# sch.net
KiCad netlist of a schematic drawn in EAGLE
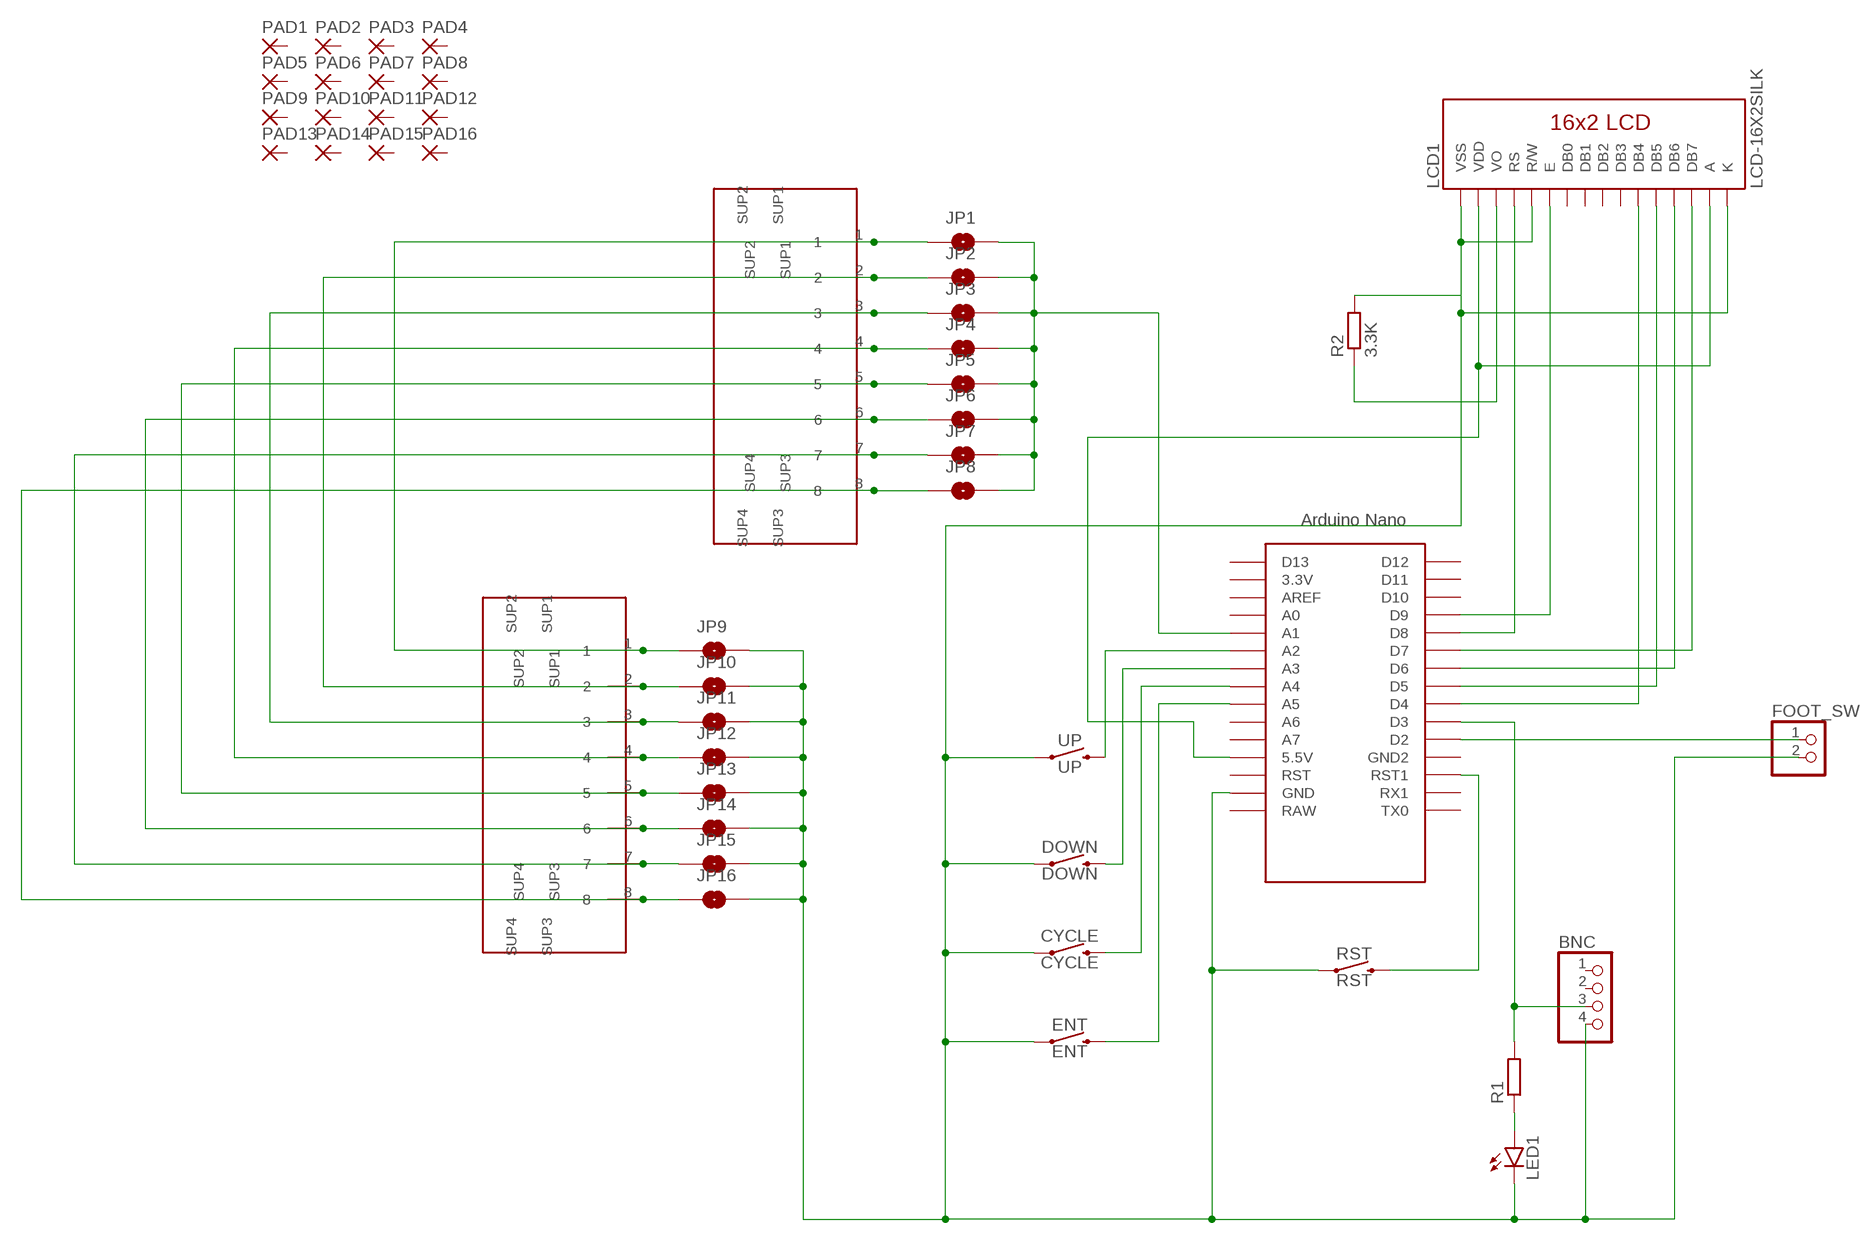
[diagram p0: schematic, sheet 1]

(export (version "E")
  (design (tool "Eeschema 10.0.6"))
  (components
    (comp (ref "BNC")
      (value "PINHD-1X4")
      (footprint "eagle-import:1X04")
      (libsource (lib "eagle-import") (part "PINHD-1X4"))
    )
    (comp (ref "CYCLE")
      (value "CYCLE")
      (footprint "eagle-import:TACTILE_SWITCH_PTH_6.0MM")
      (libsource (lib "eagle-import") (part "MOMENTARY-SWITCH-SPST-PTH-6.0MM"))
    )
    (comp (ref "DOWN")
      (value "DOWN")
      (footprint "eagle-import:TACTILE_SWITCH_PTH_6.0MM")
      (libsource (lib "eagle-import") (part "MOMENTARY-SWITCH-SPST-PTH-6.0MM"))
    )
    (comp (ref "ENT")
      (value "ENT")
      (footprint "eagle-import:TACTILE_SWITCH_PTH_6.0MM")
      (libsource (lib "eagle-import") (part "MOMENTARY-SWITCH-SPST-PTH-6.0MM"))
    )
    (comp (ref "FOOT_SW")
      (value "PINHD-1X2")
      (footprint "eagle-import:1X02")
      (libsource (lib "eagle-import") (part "PINHD-1X2"))
    )
    (comp (ref "JP1")
      (value "JUMPER-SMT_2_NO_SILK")
      (footprint "eagle-import:SMT-JUMPER_2_NO_SILK")
      (libsource (lib "eagle-import") (part "JUMPER-SMT_2_NO_SILK"))
    )
    (comp (ref "JP2")
      (value "JUMPER-SMT_2_NO_SILK")
      (footprint "eagle-import:SMT-JUMPER_2_NO_SILK")
      (libsource (lib "eagle-import") (part "JUMPER-SMT_2_NO_SILK"))
    )
    (comp (ref "JP3")
      (value "JUMPER-SMT_2_NO_SILK")
      (footprint "eagle-import:SMT-JUMPER_2_NO_SILK")
      (libsource (lib "eagle-import") (part "JUMPER-SMT_2_NO_SILK"))
    )
    (comp (ref "JP4")
      (value "JUMPER-SMT_2_NO_SILK")
      (footprint "eagle-import:SMT-JUMPER_2_NO_SILK")
      (libsource (lib "eagle-import") (part "JUMPER-SMT_2_NO_SILK"))
    )
    (comp (ref "JP5")
      (value "JUMPER-SMT_2_NO_SILK")
      (footprint "eagle-import:SMT-JUMPER_2_NO_SILK")
      (libsource (lib "eagle-import") (part "JUMPER-SMT_2_NO_SILK"))
    )
    (comp (ref "JP6")
      (value "JUMPER-SMT_2_NO_SILK")
      (footprint "eagle-import:SMT-JUMPER_2_NO_SILK")
      (libsource (lib "eagle-import") (part "JUMPER-SMT_2_NO_SILK"))
    )
    (comp (ref "JP7")
      (value "JUMPER-SMT_2_NO_SILK")
      (footprint "eagle-import:SMT-JUMPER_2_NO_SILK")
      (libsource (lib "eagle-import") (part "JUMPER-SMT_2_NO_SILK"))
    )
    (comp (ref "JP8")
      (value "JUMPER-SMT_2_NO_SILK")
      (footprint "eagle-import:SMT-JUMPER_2_NO_SILK")
      (libsource (lib "eagle-import") (part "JUMPER-SMT_2_NO_SILK"))
    )
    (comp (ref "JP9")
      (value "JUMPER-SMT_2_NO_SILK")
      (footprint "eagle-import:SMT-JUMPER_2_NO_SILK")
      (libsource (lib "eagle-import") (part "JUMPER-SMT_2_NO_SILK"))
    )
    (comp (ref "JP10")
      (value "JUMPER-SMT_2_NO_SILK")
      (footprint "eagle-import:SMT-JUMPER_2_NO_SILK")
      (libsource (lib "eagle-import") (part "JUMPER-SMT_2_NO_SILK"))
    )
    (comp (ref "JP11")
      (value "JUMPER-SMT_2_NO_SILK")
      (footprint "eagle-import:SMT-JUMPER_2_NO_SILK")
      (libsource (lib "eagle-import") (part "JUMPER-SMT_2_NO_SILK"))
    )
    (comp (ref "JP12")
      (value "JUMPER-SMT_2_NO_SILK")
      (footprint "eagle-import:SMT-JUMPER_2_NO_SILK")
      (libsource (lib "eagle-import") (part "JUMPER-SMT_2_NO_SILK"))
    )
    (comp (ref "JP13")
      (value "JUMPER-SMT_2_NO_SILK")
      (footprint "eagle-import:SMT-JUMPER_2_NO_SILK")
      (libsource (lib "eagle-import") (part "JUMPER-SMT_2_NO_SILK"))
    )
    (comp (ref "JP14")
      (value "JUMPER-SMT_2_NO_SILK")
      (footprint "eagle-import:SMT-JUMPER_2_NO_SILK")
      (libsource (lib "eagle-import") (part "JUMPER-SMT_2_NO_SILK"))
    )
    (comp (ref "JP15")
      (value "JUMPER-SMT_2_NO_SILK")
      (footprint "eagle-import:SMT-JUMPER_2_NO_SILK")
      (libsource (lib "eagle-import") (part "JUMPER-SMT_2_NO_SILK"))
    )
    (comp (ref "JP16")
      (value "JUMPER-SMT_2_NO_SILK")
      (footprint "eagle-import:SMT-JUMPER_2_NO_SILK")
      (libsource (lib "eagle-import") (part "JUMPER-SMT_2_NO_SILK"))
    )
    (comp (ref "LAN1")
      (value "RJ45")
      (footprint "eagle-import:RJ45")
      (libsource (lib "eagle-import") (part "RJ45"))
    )
    (comp (ref "LAN2")
      (value "RJ45")
      (footprint "eagle-import:RJ45")
      (libsource (lib "eagle-import") (part "RJ45"))
    )
    (comp (ref "LCD1")
      (value "LCD-16X2SILK")
      (footprint "eagle-import:LCD-16X2")
      (libsource (lib "eagle-import") (part "LCD-16X2SILK"))
    )
    (comp (ref "LED1")
      (value "LED5MM")
      (footprint "eagle-import:LED5MM")
      (libsource (lib "eagle-import") (part "LED5MM"))
    )
    (comp (ref "PAD1")
      (value "1,6/0,8")
      (footprint "eagle-import:1,6_0,8")
      (libsource (lib "eagle-import") (part "1,6/0,8"))
    )
    (comp (ref "PAD2")
      (value "1,6/0,8")
      (footprint "eagle-import:1,6_0,8")
      (libsource (lib "eagle-import") (part "1,6/0,8"))
    )
    (comp (ref "PAD3")
      (value "1,6/0,8")
      (footprint "eagle-import:1,6_0,8")
      (libsource (lib "eagle-import") (part "1,6/0,8"))
    )
    (comp (ref "PAD4")
      (value "1,6/0,8")
      (footprint "eagle-import:1,6_0,8")
      (libsource (lib "eagle-import") (part "1,6/0,8"))
    )
    (comp (ref "PAD5")
      (value "1,6/0,8")
      (footprint "eagle-import:1,6_0,8")
      (libsource (lib "eagle-import") (part "1,6/0,8"))
    )
    (comp (ref "PAD6")
      (value "1,6/0,8")
      (footprint "eagle-import:1,6_0,8")
      (libsource (lib "eagle-import") (part "1,6/0,8"))
    )
    (comp (ref "PAD7")
      (value "1,6/0,8")
      (footprint "eagle-import:1,6_0,8")
      (libsource (lib "eagle-import") (part "1,6/0,8"))
    )
    (comp (ref "PAD8")
      (value "1,6/0,8")
      (footprint "eagle-import:1,6_0,8")
      (libsource (lib "eagle-import") (part "1,6/0,8"))
    )
    (comp (ref "PAD9")
      (value "1,6/0,8")
      (footprint "eagle-import:1,6_0,8")
      (libsource (lib "eagle-import") (part "1,6/0,8"))
    )
    (comp (ref "PAD10")
      (value "1,6/0,8")
      (footprint "eagle-import:1,6_0,8")
      (libsource (lib "eagle-import") (part "1,6/0,8"))
    )
    (comp (ref "PAD11")
      (value "1,6/0,8")
      (footprint "eagle-import:1,6_0,8")
      (libsource (lib "eagle-import") (part "1,6/0,8"))
    )
    (comp (ref "PAD12")
      (value "1,6/0,8")
      (footprint "eagle-import:1,6_0,8")
      (libsource (lib "eagle-import") (part "1,6/0,8"))
    )
    (comp (ref "PAD13")
      (value "1,6/0,8")
      (footprint "eagle-import:1,6_0,8")
      (libsource (lib "eagle-import") (part "1,6/0,8"))
    )
    (comp (ref "PAD14")
      (value "1,6/0,8")
      (footprint "eagle-import:1,6_0,8")
      (libsource (lib "eagle-import") (part "1,6/0,8"))
    )
    (comp (ref "PAD15")
      (value "1,6/0,8")
      (footprint "eagle-import:1,6_0,8")
      (libsource (lib "eagle-import") (part "1,6/0,8"))
    )
    (comp (ref "PAD16")
      (value "1,6/0,8")
      (footprint "eagle-import:1,6_0,8")
      (libsource (lib "eagle-import") (part "1,6/0,8"))
    )
    (comp (ref "R1")
      (value "R-EU_0207/7")
      (footprint "eagle-import:0207_7")
      (libsource (lib "eagle-import") (part "R-EU_0207/7"))
    )
    (comp (ref "R2")
      (value "3.3K")
      (footprint "eagle-import:0207_7")
      (libsource (lib "eagle-import") (part "R-EU_0207/7"))
    )
    (comp (ref "RST")
      (value "RST")
      (footprint "eagle-import:TACTILE_SWITCH_PTH_6.0MM")
      (libsource (lib "eagle-import") (part "MOMENTARY-SWITCH-SPST-PTH-6.0MM"))
    )
    (comp (ref "U$1")
      (value "NANO")
      (footprint "eagle-import:NANO")
      (libsource (lib "eagle-import") (part "NANO"))
    )
    (comp (ref "UP")
      (value "UP")
      (footprint "eagle-import:TACTILE_SWITCH_PTH_6.0MM")
      (libsource (lib "eagle-import") (part "MOMENTARY-SWITCH-SPST-PTH-6.0MM"))
    )
  )
  (nets
    (net (code "1") (name "Net-(BNC-Pad3)") (class "Default")
      (node (ref "BNC") (pin "3") (pinfunction "3_3") (pintype "passive"))
      (node (ref "R1") (pin "2") (pinfunction "2_2") (pintype "passive"))
      (node (ref "U$1") (pin "D3") (pinfunction "D3_D3") (pintype "bidirectional"))
    )
    (net (code "2") (name "Net-(CYCLE-2)") (class "Default")
      (node (ref "CYCLE") (pin "3") (pinfunction "2_3") (pintype "passive"))
      (node (ref "U$1") (pin "A4") (pinfunction "A4_A4") (pintype "bidirectional"))
    )
    (net (code "3") (name "Net-(DOWN-2)") (class "Default")
      (node (ref "DOWN") (pin "3") (pinfunction "2_3") (pintype "passive"))
      (node (ref "U$1") (pin "A3") (pinfunction "A3_A3") (pintype "bidirectional"))
    )
    (net (code "4") (name "Net-(ENT-2)") (class "Default")
      (node (ref "ENT") (pin "3") (pinfunction "2_3") (pintype "passive"))
      (node (ref "U$1") (pin "A5") (pinfunction "A5_A5") (pintype "bidirectional"))
    )
    (net (code "5") (name "Net-(FOOT_SW-Pad1)") (class "Default")
      (node (ref "FOOT_SW") (pin "1") (pinfunction "1_1") (pintype "passive"))
      (node (ref "U$1") (pin "D2") (pinfunction "D2_D2") (pintype "bidirectional"))
    )
    (net (code "6") (name "Net-(JP1-Pad1)") (class "Default")
      (node (ref "JP1") (pin "1") (pinfunction "1_1") (pintype "passive"))
      (node (ref "JP9") (pin "1") (pinfunction "1_1") (pintype "passive"))
      (node (ref "LAN1") (pin "1") (pinfunction "1_1") (pintype "bidirectional"))
      (node (ref "LAN2") (pin "1") (pinfunction "1_1") (pintype "bidirectional"))
    )
    (net (code "7") (name "Net-(JP1-Pad2)") (class "Default")
      (node (ref "JP1") (pin "2") (pinfunction "2_2") (pintype "passive"))
      (node (ref "JP2") (pin "2") (pinfunction "2_2") (pintype "passive"))
      (node (ref "JP3") (pin "2") (pinfunction "2_2") (pintype "passive"))
      (node (ref "JP4") (pin "2") (pinfunction "2_2") (pintype "passive"))
      (node (ref "JP5") (pin "2") (pinfunction "2_2") (pintype "passive"))
      (node (ref "JP6") (pin "2") (pinfunction "2_2") (pintype "passive"))
      (node (ref "JP7") (pin "2") (pinfunction "2_2") (pintype "passive"))
      (node (ref "JP8") (pin "2") (pinfunction "2_2") (pintype "passive"))
      (node (ref "U$1") (pin "A1") (pinfunction "A1_A1") (pintype "bidirectional"))
    )
    (net (code "8") (name "Net-(JP10-Pad1)") (class "Default")
      (node (ref "JP10") (pin "1") (pinfunction "1_1") (pintype "passive"))
      (node (ref "JP2") (pin "1") (pinfunction "1_1") (pintype "passive"))
      (node (ref "LAN1") (pin "2") (pinfunction "2_2") (pintype "bidirectional"))
      (node (ref "LAN2") (pin "2") (pinfunction "2_2") (pintype "bidirectional"))
    )
    (net (code "9") (name "Net-(JP11-Pad1)") (class "Default")
      (node (ref "JP11") (pin "1") (pinfunction "1_1") (pintype "passive"))
      (node (ref "JP3") (pin "1") (pinfunction "1_1") (pintype "passive"))
      (node (ref "LAN1") (pin "3") (pinfunction "3_3") (pintype "bidirectional"))
      (node (ref "LAN2") (pin "3") (pinfunction "3_3") (pintype "bidirectional"))
    )
    (net (code "10") (name "Net-(JP12-Pad1)") (class "Default")
      (node (ref "JP12") (pin "1") (pinfunction "1_1") (pintype "passive"))
      (node (ref "JP4") (pin "1") (pinfunction "1_1") (pintype "passive"))
      (node (ref "LAN1") (pin "4") (pinfunction "4_4") (pintype "bidirectional"))
      (node (ref "LAN2") (pin "4") (pinfunction "4_4") (pintype "bidirectional"))
    )
    (net (code "11") (name "Net-(JP13-Pad1)") (class "Default")
      (node (ref "JP13") (pin "1") (pinfunction "1_1") (pintype "passive"))
      (node (ref "JP5") (pin "1") (pinfunction "1_1") (pintype "passive"))
      (node (ref "LAN1") (pin "5") (pinfunction "5_5") (pintype "bidirectional"))
      (node (ref "LAN2") (pin "5") (pinfunction "5_5") (pintype "bidirectional"))
    )
    (net (code "12") (name "Net-(JP14-Pad1)") (class "Default")
      (node (ref "JP14") (pin "1") (pinfunction "1_1") (pintype "passive"))
      (node (ref "JP6") (pin "1") (pinfunction "1_1") (pintype "passive"))
      (node (ref "LAN1") (pin "6") (pinfunction "6_6") (pintype "bidirectional"))
      (node (ref "LAN2") (pin "6") (pinfunction "6_6") (pintype "bidirectional"))
    )
    (net (code "13") (name "Net-(JP15-Pad1)") (class "Default")
      (node (ref "JP15") (pin "1") (pinfunction "1_1") (pintype "passive"))
      (node (ref "JP7") (pin "1") (pinfunction "1_1") (pintype "passive"))
      (node (ref "LAN1") (pin "7") (pinfunction "7_7") (pintype "bidirectional"))
      (node (ref "LAN2") (pin "7") (pinfunction "7_7") (pintype "bidirectional"))
    )
    (net (code "14") (name "Net-(JP16-Pad1)") (class "Default")
      (node (ref "JP16") (pin "1") (pinfunction "1_1") (pintype "passive"))
      (node (ref "JP8") (pin "1") (pinfunction "1_1") (pintype "passive"))
      (node (ref "LAN1") (pin "8") (pinfunction "8_8") (pintype "bidirectional"))
      (node (ref "LAN2") (pin "8") (pinfunction "8_8") (pintype "bidirectional"))
    )
    (net (code "15") (name "Net-(LCD1-A)") (class "Default")
      (node (ref "LCD1") (pin "15") (pinfunction "A_15") (pintype "power_in"))
      (node (ref "LCD1") (pin "2") (pinfunction "VDD_2") (pintype "power_in"))
      (node (ref "U$1") (pin "5V") (pinfunction "5.5V_5V") (pintype "bidirectional"))
    )
    (net (code "16") (name "Net-(LCD1-DB4)") (class "Default")
      (node (ref "LCD1") (pin "11") (pinfunction "DB4_11") (pintype "bidirectional"))
      (node (ref "U$1") (pin "D4") (pinfunction "D4_D4") (pintype "bidirectional"))
    )
    (net (code "17") (name "Net-(LCD1-DB5)") (class "Default")
      (node (ref "LCD1") (pin "12") (pinfunction "DB5_12") (pintype "bidirectional"))
      (node (ref "U$1") (pin "D5") (pinfunction "D5_D5") (pintype "bidirectional"))
    )
    (net (code "18") (name "Net-(LCD1-DB6)") (class "Default")
      (node (ref "LCD1") (pin "13") (pinfunction "DB6_13") (pintype "bidirectional"))
      (node (ref "U$1") (pin "D6") (pinfunction "D6_D6") (pintype "bidirectional"))
    )
    (net (code "19") (name "Net-(LCD1-DB7)") (class "Default")
      (node (ref "LCD1") (pin "14") (pinfunction "DB7_14") (pintype "bidirectional"))
      (node (ref "U$1") (pin "D7") (pinfunction "D7_D7") (pintype "bidirectional"))
    )
    (net (code "20") (name "Net-(LCD1-E)") (class "Default")
      (node (ref "LCD1") (pin "6") (pinfunction "E_6") (pintype "input"))
      (node (ref "U$1") (pin "D9") (pinfunction "D9_D9") (pintype "bidirectional"))
    )
    (net (code "21") (name "Net-(LCD1-K)") (class "Default")
      (node (ref "BNC") (pin "4") (pinfunction "4_4") (pintype "passive"))
      (node (ref "CYCLE") (pin "1") (pinfunction "1_1") (pintype "passive"))
      (node (ref "DOWN") (pin "1") (pinfunction "1_1") (pintype "passive"))
      (node (ref "ENT") (pin "1") (pinfunction "1_1") (pintype "passive"))
      (node (ref "FOOT_SW") (pin "2") (pinfunction "2_2") (pintype "passive"))
      (node (ref "JP10") (pin "2") (pinfunction "2_2") (pintype "passive"))
      (node (ref "JP11") (pin "2") (pinfunction "2_2") (pintype "passive"))
      (node (ref "JP12") (pin "2") (pinfunction "2_2") (pintype "passive"))
      (node (ref "JP13") (pin "2") (pinfunction "2_2") (pintype "passive"))
      (node (ref "JP14") (pin "2") (pinfunction "2_2") (pintype "passive"))
      (node (ref "JP15") (pin "2") (pinfunction "2_2") (pintype "passive"))
      (node (ref "JP16") (pin "2") (pinfunction "2_2") (pintype "passive"))
      (node (ref "JP9") (pin "2") (pinfunction "2_2") (pintype "passive"))
      (node (ref "LCD1") (pin "1") (pinfunction "VSS_1") (pintype "power_in"))
      (node (ref "LCD1") (pin "16") (pinfunction "K_16") (pintype "power_in"))
      (node (ref "LCD1") (pin "5") (pinfunction "R/W_5") (pintype "input"))
      (node (ref "LED1") (pin "K") (pinfunction "C_K") (pintype "passive"))
      (node (ref "R2") (pin "2") (pinfunction "2_2") (pintype "passive"))
      (node (ref "RST") (pin "1") (pinfunction "1_1") (pintype "passive"))
      (node (ref "U$1") (pin "GND") (pinfunction "GND_GND") (pintype "bidirectional"))
      (node (ref "UP") (pin "1") (pinfunction "1_1") (pintype "passive"))
    )
    (net (code "22") (name "Net-(LCD1-RS)") (class "Default")
      (node (ref "LCD1") (pin "4") (pinfunction "RS_4") (pintype "input"))
      (node (ref "U$1") (pin "D8") (pinfunction "D8_D8") (pintype "bidirectional"))
    )
    (net (code "23") (name "Net-(LCD1-VO)") (class "Default")
      (node (ref "LCD1") (pin "3") (pinfunction "VO_3") (pintype "bidirectional"))
      (node (ref "R2") (pin "1") (pinfunction "1_1") (pintype "passive"))
    )
    (net (code "24") (name "Net-(LED1-PadA)") (class "Default")
      (node (ref "LED1") (pin "A") (pinfunction "A_A") (pintype "passive"))
      (node (ref "R1") (pin "1") (pinfunction "1_1") (pintype "passive"))
    )
    (net (code "25") (name "Net-(RST-2)") (class "Default")
      (node (ref "RST") (pin "3") (pinfunction "2_3") (pintype "passive"))
      (node (ref "U$1") (pin "RST1") (pinfunction "RST1_RST1") (pintype "bidirectional"))
    )
    (net (code "26") (name "Net-(UP-2)") (class "Default")
      (node (ref "U$1") (pin "A2") (pinfunction "A2_A2") (pintype "bidirectional"))
      (node (ref "UP") (pin "3") (pinfunction "2_3") (pintype "passive"))
    )
    (net (code "27") (name "unconnected-(BNC-Pad1)") (class "Default")
      (node (ref "BNC") (pin "1") (pinfunction "1_1") (pintype "passive"))
    )
    (net (code "28") (name "unconnected-(BNC-Pad2)") (class "Default")
      (node (ref "BNC") (pin "2") (pinfunction "2_2") (pintype "passive"))
    )
    (net (code "29") (name "unconnected-(LAN1-PadSUP1)") (class "Default")
      (node (ref "LAN1") (pin "SUP1") (pinfunction "SUP1_SUP1") (pintype "bidirectional"))
    )
    (net (code "30") (name "unconnected-(LAN1-PadSUP2)") (class "Default")
      (node (ref "LAN1") (pin "SUP2") (pinfunction "SUP2_SUP2") (pintype "bidirectional"))
    )
    (net (code "31") (name "unconnected-(LAN1-PadSUP3)") (class "Default")
      (node (ref "LAN1") (pin "SUP3") (pinfunction "SUP3_SUP3") (pintype "bidirectional"))
    )
    (net (code "32") (name "unconnected-(LAN1-PadSUP4)") (class "Default")
      (node (ref "LAN1") (pin "SUP4") (pinfunction "SUP4_SUP4") (pintype "bidirectional"))
    )
    (net (code "33") (name "unconnected-(LAN2-PadSUP1)") (class "Default")
      (node (ref "LAN2") (pin "SUP1") (pinfunction "SUP1_SUP1") (pintype "bidirectional"))
    )
    (net (code "34") (name "unconnected-(LAN2-PadSUP2)") (class "Default")
      (node (ref "LAN2") (pin "SUP2") (pinfunction "SUP2_SUP2") (pintype "bidirectional"))
    )
    (net (code "35") (name "unconnected-(LAN2-PadSUP3)") (class "Default")
      (node (ref "LAN2") (pin "SUP3") (pinfunction "SUP3_SUP3") (pintype "bidirectional"))
    )
    (net (code "36") (name "unconnected-(LAN2-PadSUP4)") (class "Default")
      (node (ref "LAN2") (pin "SUP4") (pinfunction "SUP4_SUP4") (pintype "bidirectional"))
    )
    (net (code "37") (name "unconnected-(LCD1-DB0-Pad7)") (class "Default")
      (node (ref "LCD1") (pin "7") (pinfunction "DB0_7") (pintype "bidirectional"))
    )
    (net (code "38") (name "unconnected-(LCD1-DB1-Pad8)") (class "Default")
      (node (ref "LCD1") (pin "8") (pinfunction "DB1_8") (pintype "bidirectional"))
    )
    (net (code "39") (name "unconnected-(LCD1-DB2-Pad9)") (class "Default")
      (node (ref "LCD1") (pin "9") (pinfunction "DB2_9") (pintype "bidirectional"))
    )
    (net (code "40") (name "unconnected-(LCD1-DB3-Pad10)") (class "Default")
      (node (ref "LCD1") (pin "10") (pinfunction "DB3_10") (pintype "bidirectional"))
    )
    (net (code "41") (name "unconnected-(PAD1-P-Pad1)") (class "Default")
      (node (ref "PAD1") (pin "1") (pinfunction "P_1") (pintype "passive"))
    )
    (net (code "42") (name "unconnected-(PAD2-P-Pad1)") (class "Default")
      (node (ref "PAD2") (pin "1") (pinfunction "P_1") (pintype "passive"))
    )
    (net (code "43") (name "unconnected-(PAD3-P-Pad1)") (class "Default")
      (node (ref "PAD3") (pin "1") (pinfunction "P_1") (pintype "passive"))
    )
    (net (code "44") (name "unconnected-(PAD4-P-Pad1)") (class "Default")
      (node (ref "PAD4") (pin "1") (pinfunction "P_1") (pintype "passive"))
    )
    (net (code "45") (name "unconnected-(PAD5-P-Pad1)") (class "Default")
      (node (ref "PAD5") (pin "1") (pinfunction "P_1") (pintype "passive"))
    )
    (net (code "46") (name "unconnected-(PAD6-P-Pad1)") (class "Default")
      (node (ref "PAD6") (pin "1") (pinfunction "P_1") (pintype "passive"))
    )
    (net (code "47") (name "unconnected-(PAD7-P-Pad1)") (class "Default")
      (node (ref "PAD7") (pin "1") (pinfunction "P_1") (pintype "passive"))
    )
    (net (code "48") (name "unconnected-(PAD8-P-Pad1)") (class "Default")
      (node (ref "PAD8") (pin "1") (pinfunction "P_1") (pintype "passive"))
    )
    (net (code "49") (name "unconnected-(PAD9-P-Pad1)") (class "Default")
      (node (ref "PAD9") (pin "1") (pinfunction "P_1") (pintype "passive"))
    )
    (net (code "50") (name "unconnected-(PAD10-P-Pad1)") (class "Default")
      (node (ref "PAD10") (pin "1") (pinfunction "P_1") (pintype "passive"))
    )
    (net (code "51") (name "unconnected-(PAD11-P-Pad1)") (class "Default")
      (node (ref "PAD11") (pin "1") (pinfunction "P_1") (pintype "passive"))
    )
    (net (code "52") (name "unconnected-(PAD12-P-Pad1)") (class "Default")
      (node (ref "PAD12") (pin "1") (pinfunction "P_1") (pintype "passive"))
    )
    (net (code "53") (name "unconnected-(PAD13-P-Pad1)") (class "Default")
      (node (ref "PAD13") (pin "1") (pinfunction "P_1") (pintype "passive"))
    )
    (net (code "54") (name "unconnected-(PAD14-P-Pad1)") (class "Default")
      (node (ref "PAD14") (pin "1") (pinfunction "P_1") (pintype "passive"))
    )
    (net (code "55") (name "unconnected-(PAD15-P-Pad1)") (class "Default")
      (node (ref "PAD15") (pin "1") (pinfunction "P_1") (pintype "passive"))
    )
    (net (code "56") (name "unconnected-(PAD16-P-Pad1)") (class "Default")
      (node (ref "PAD16") (pin "1") (pinfunction "P_1") (pintype "passive"))
    )
    (net (code "57") (name "unconnected-(U$1-GND2-PadGND1)") (class "Default")
      (node (ref "U$1") (pin "GND1") (pinfunction "GND2_GND1") (pintype "bidirectional"))
    )
    (net (code "58") (name "unconnected-(U$1-Pad3.3V)") (class "Default")
      (node (ref "U$1") (pin "3.3V") (pinfunction "3.3V_3.3V") (pintype "bidirectional"))
    )
    (net (code "59") (name "unconnected-(U$1-PadA0)") (class "Default")
      (node (ref "U$1") (pin "A0") (pinfunction "A0_A0") (pintype "bidirectional"))
    )
    (net (code "60") (name "unconnected-(U$1-PadA6)") (class "Default")
      (node (ref "U$1") (pin "A6") (pinfunction "A6_A6") (pintype "bidirectional"))
    )
    (net (code "61") (name "unconnected-(U$1-PadA7)") (class "Default")
      (node (ref "U$1") (pin "A7") (pinfunction "A7_A7") (pintype "bidirectional"))
    )
    (net (code "62") (name "unconnected-(U$1-PadAREF)") (class "Default")
      (node (ref "U$1") (pin "AREF") (pinfunction "AREF_AREF") (pintype "bidirectional"))
    )
    (net (code "63") (name "unconnected-(U$1-PadD10)") (class "Default")
      (node (ref "U$1") (pin "D10") (pinfunction "D10_D10") (pintype "bidirectional"))
    )
    (net (code "64") (name "unconnected-(U$1-PadD11)") (class "Default")
      (node (ref "U$1") (pin "D11") (pinfunction "D11_D11") (pintype "bidirectional"))
    )
    (net (code "65") (name "unconnected-(U$1-PadD12)") (class "Default")
      (node (ref "U$1") (pin "D12") (pinfunction "D12_D12") (pintype "bidirectional"))
    )
    (net (code "66") (name "unconnected-(U$1-PadD13)") (class "Default")
      (node (ref "U$1") (pin "D13") (pinfunction "D13_D13") (pintype "bidirectional"))
    )
    (net (code "67") (name "unconnected-(U$1-PadICSP1)") (class "Default")
      (node (ref "U$1") (pin "ICSP1") (pinfunction "ICSP1_ICSP1") (pintype "bidirectional"))
    )
    (net (code "68") (name "unconnected-(U$1-PadICSP2)") (class "Default")
      (node (ref "U$1") (pin "ICSP2") (pinfunction "ICSP2_ICSP2") (pintype "bidirectional"))
    )
    (net (code "69") (name "unconnected-(U$1-PadICSP3)") (class "Default")
      (node (ref "U$1") (pin "ICSP3") (pinfunction "ICSP3_ICSP3") (pintype "bidirectional"))
    )
    (net (code "70") (name "unconnected-(U$1-PadICSP4)") (class "Default")
      (node (ref "U$1") (pin "ICSP4") (pinfunction "ICSP4_ICSP4") (pintype "bidirectional"))
    )
    (net (code "71") (name "unconnected-(U$1-PadICSP5)") (class "Default")
      (node (ref "U$1") (pin "ICSP5") (pinfunction "ICSP5_ICSP5") (pintype "bidirectional"))
    )
    (net (code "72") (name "unconnected-(U$1-PadICSP6)") (class "Default")
      (node (ref "U$1") (pin "ICSP6") (pinfunction "ICSP6_ICSP6") (pintype "bidirectional"))
    )
    (net (code "73") (name "unconnected-(U$1-PadRAW)") (class "Default")
      (node (ref "U$1") (pin "RAW") (pinfunction "RAW_RAW") (pintype "bidirectional"))
    )
    (net (code "74") (name "unconnected-(U$1-PadRST)") (class "Default")
      (node (ref "U$1") (pin "RST") (pinfunction "RST_RST") (pintype "bidirectional"))
    )
    (net (code "75") (name "unconnected-(U$1-PadRX1)") (class "Default")
      (node (ref "U$1") (pin "RX1") (pinfunction "RX1_RX1") (pintype "bidirectional"))
    )
    (net (code "76") (name "unconnected-(U$1-PadTX0)") (class "Default")
      (node (ref "U$1") (pin "TX0") (pinfunction "TX0_TX0") (pintype "bidirectional"))
    )
  )
)
